# EndEffector.net
KiCad netlist of a schematic drawn in EAGLE
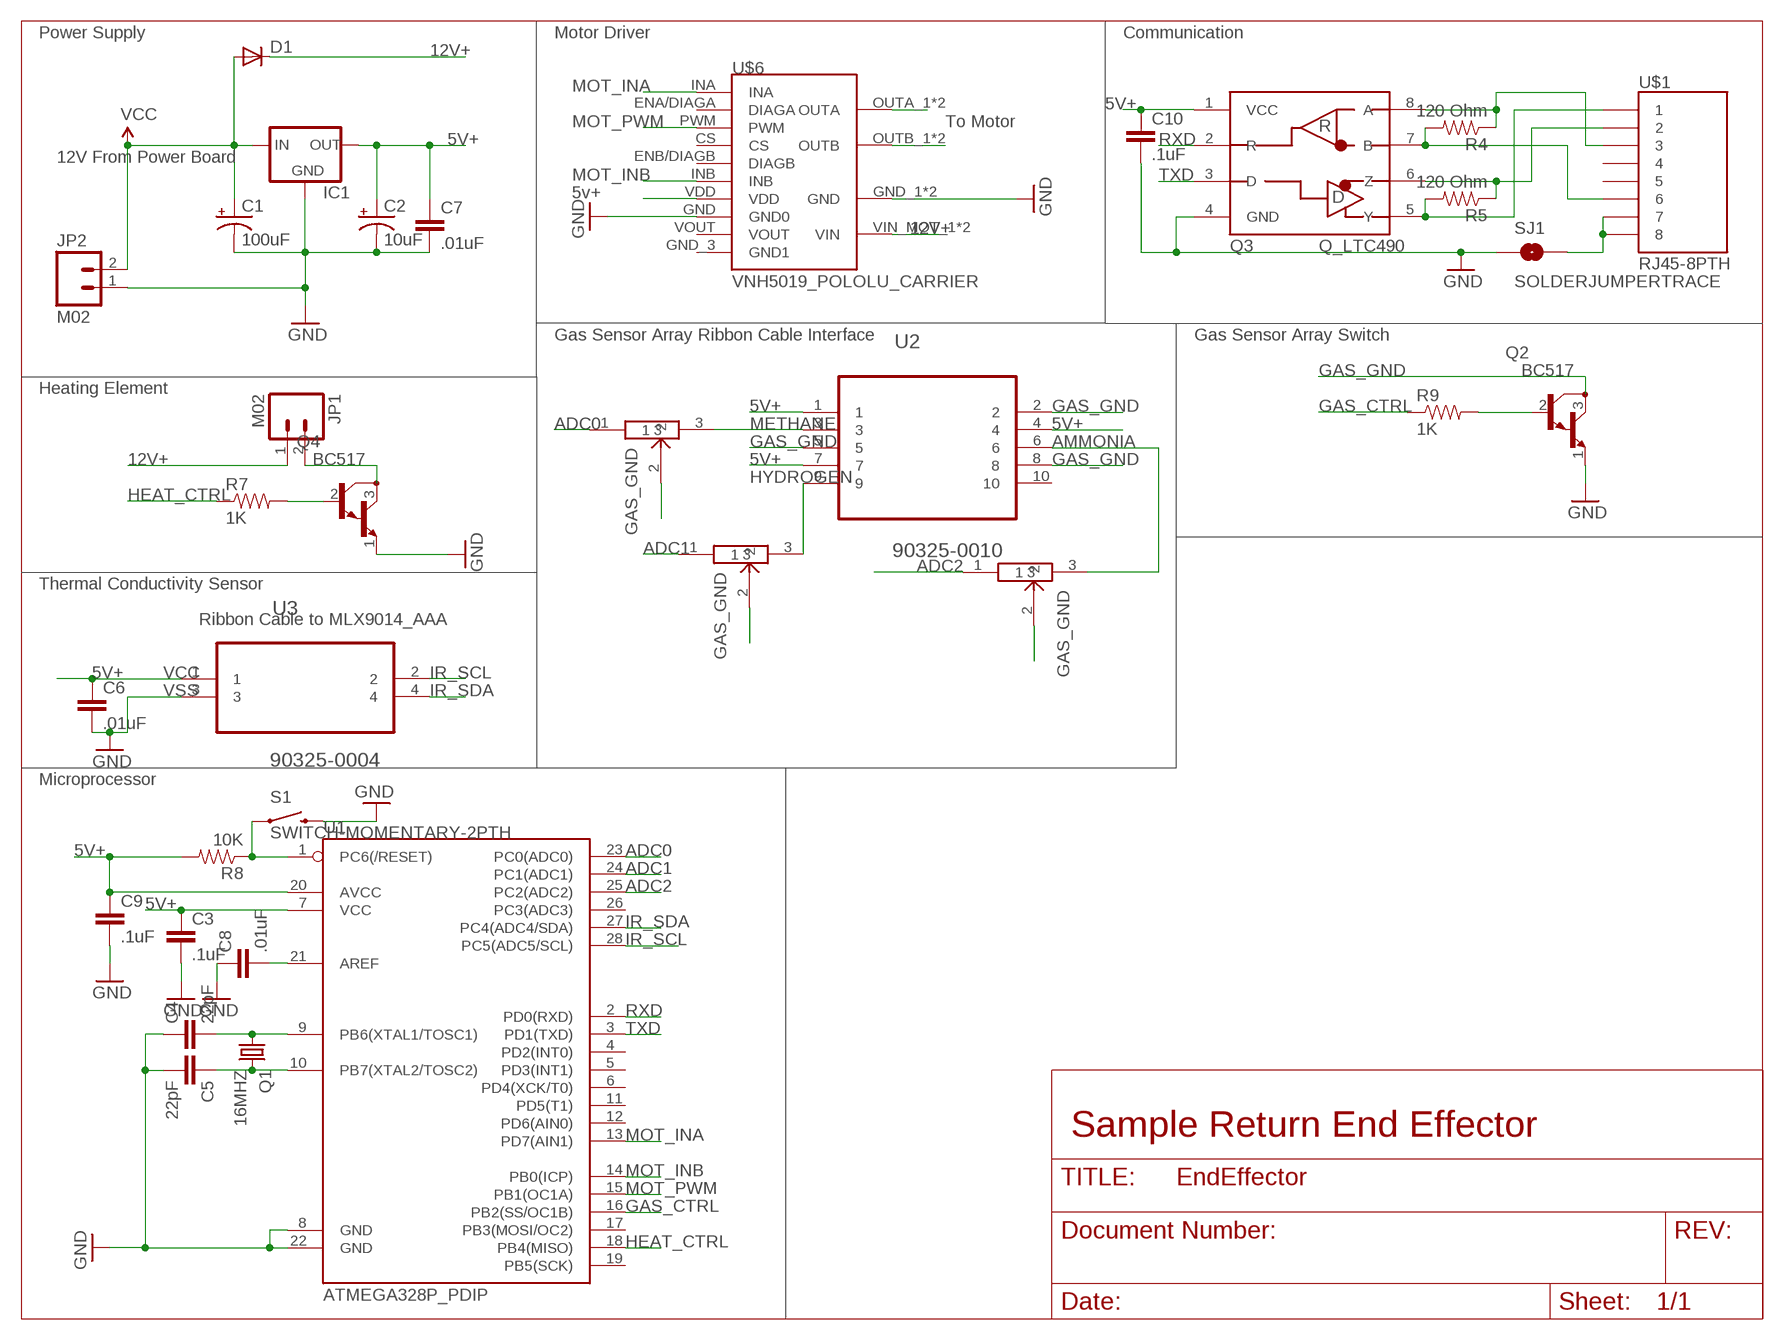
[diagram p0: schematic, sheet 1]

(export (version "E")
  (design (tool "Eeschema 10.0.6"))
  (components
    (comp (ref "C1")
      (value "100uF")
      (footprint "eagle-import:CPOL-RADIAL-100UF-25V")
      (libsource (lib "eagle-import") (part "CAP_POLPTH1"))
    )
    (comp (ref "C2")
      (value "10uF")
      (footprint "eagle-import:CPOL-RADIAL-10UF-25V")
      (libsource (lib "eagle-import") (part "CAP_POLPTH2"))
    )
    (comp (ref "C3")
      (value ".1uF")
      (footprint "eagle-import:CAP-PTH-SMALL-KIT")
      (libsource (lib "eagle-import") (part "CAPKIT"))
    )
    (comp (ref "C4")
      (value "22pF")
      (footprint "eagle-import:CAP-PTH-SMALL-KIT")
      (libsource (lib "eagle-import") (part "CAPKIT"))
    )
    (comp (ref "C5")
      (value "22pF")
      (footprint "eagle-import:CAP-PTH-SMALL-KIT")
      (libsource (lib "eagle-import") (part "CAPKIT"))
    )
    (comp (ref "C6")
      (value ".01uF")
      (footprint "eagle-import:CAP-PTH-SMALL-KIT")
      (libsource (lib "eagle-import") (part "CAPKIT"))
    )
    (comp (ref "C7")
      (value ".01uF")
      (footprint "eagle-import:CAP-PTH-SMALL-KIT")
      (libsource (lib "eagle-import") (part "CAPKIT"))
    )
    (comp (ref "C8")
      (value ".01uF")
      (footprint "eagle-import:CAP-PTH-SMALL-KIT")
      (libsource (lib "eagle-import") (part "CAPKIT"))
    )
    (comp (ref "C9")
      (value ".1uF")
      (footprint "eagle-import:CAP-PTH-SMALL-KIT")
      (libsource (lib "eagle-import") (part "CAPKIT"))
    )
    (comp (ref "C10")
      (value ".1uF")
      (footprint "eagle-import:CAP-PTH-SMALL-KIT")
      (libsource (lib "eagle-import") (part "CAPKIT"))
    )
    (comp (ref "D1")
      (value "DIODEPTH")
      (footprint "eagle-import:DIODE-1N4001")
      (libsource (lib "eagle-import") (part "DIODEPTH"))
    )
    (comp (ref "IC1")
      (value "V_REG_78XXSINK")
      (footprint "eagle-import:TO220-IGO")
      (libsource (lib "eagle-import") (part "V_REG_78XXSINK"))
    )
    (comp (ref "JP1")
      (value "M02")
      (footprint "eagle-import:1X02_PP_HOLES_ONLY")
      (libsource (lib "eagle-import") (part "M02POGO_PIN_HOLES_ONLY"))
    )
    (comp (ref "JP2")
      (value "M02")
      (footprint "eagle-import:1X02_PP_HOLES_ONLY")
      (libsource (lib "eagle-import") (part "M02POGO_PIN_HOLES_ONLY"))
    )
    (comp (ref "Q1")
      (value "16MHZ")
      (footprint "eagle-import:HC49_S")
      (libsource (lib "eagle-import") (part "CRYSTALHC49S"))
    )
    (comp (ref "Q2")
      (value "BC517")
      (footprint "eagle-import:TO92")
      (libsource (lib "eagle-import") (part "BC517"))
    )
    (comp (ref "Q3")
      (value "Q_LTC490")
      (footprint "eagle-import:DIP8")
      (libsource (lib "eagle-import") (part "Q_LTC490"))
    )
    (comp (ref "Q4")
      (value "BC517")
      (footprint "eagle-import:TO92")
      (libsource (lib "eagle-import") (part "BC517"))
    )
    (comp (ref "R4")
      (value "120 Ohm")
      (footprint "eagle-import:AXIAL-0.3")
      (libsource (lib "eagle-import") (part "RESISTORAXIAL-0.3"))
    )
    (comp (ref "R5")
      (value "120 Ohm")
      (footprint "eagle-import:AXIAL-0.3")
      (libsource (lib "eagle-import") (part "RESISTORAXIAL-0.3"))
    )
    (comp (ref "R7")
      (value "1K")
      (footprint "eagle-import:AXIAL-0.3")
      (libsource (lib "eagle-import") (part "RESISTORAXIAL-0.3"))
    )
    (comp (ref "R8")
      (value "10K")
      (footprint "eagle-import:AXIAL-0.3")
      (libsource (lib "eagle-import") (part "RESISTORAXIAL-0.3"))
    )
    (comp (ref "R9")
      (value "1K")
      (footprint "eagle-import:AXIAL-0.3")
      (libsource (lib "eagle-import") (part "RESISTORAXIAL-0.3"))
    )
    (comp (ref "S1")
      (value "SWITCH-MOMENTARY-2PTH")
      (footprint "eagle-import:TACTILE-PTH")
      (libsource (lib "eagle-import") (part "SWITCH-MOMENTARY-2PTH"))
    )
    (comp (ref "SJ1")
      (value "SOLDERJUMPERTRACE")
      (footprint "eagle-import:SJ_2S-TRACE")
      (libsource (lib "eagle-import") (part "SOLDERJUMPERTRACE"))
    )
    (comp (ref "U$1")
      (value "RJ45-8PTH")
      (footprint "eagle-import:RJ45-8")
      (libsource (lib "eagle-import") (part "RJ45-8PTH"))
    )
    (comp (ref "U$2")
      (value "POTENTIOMETER_BOURNS_3006P-1-104LF")
      (footprint "eagle-import:BOURNS30006_TRIMPOT")
      (libsource (lib "eagle-import") (part "POTENTIOMETER_BOURNS_3006P-1-104LF"))
    )
    (comp (ref "U$4")
      (value "POTENTIOMETER_BOURNS_3006P-1-104LF")
      (footprint "eagle-import:BOURNS30006_TRIMPOT")
      (libsource (lib "eagle-import") (part "POTENTIOMETER_BOURNS_3006P-1-104LF"))
    )
    (comp (ref "U$5")
      (value "POTENTIOMETER_BOURNS_3006P-1-104LF")
      (footprint "eagle-import:BOURNS30006_TRIMPOT")
      (libsource (lib "eagle-import") (part "POTENTIOMETER_BOURNS_3006P-1-104LF"))
    )
    (comp (ref "U$6")
      (value "VNH5019_POLOLU_CARRIER")
      (footprint "eagle-import:VNH5019_CARRIER")
      (libsource (lib "eagle-import") (part "VNH5019_POLOLU_CARRIER"))
    )
    (comp (ref "U1")
      (value "ATMEGA328P_PDIP")
      (footprint "eagle-import:DIL28-3")
      (libsource (lib "eagle-import") (part "ATMEGA328P_PDIP"))
    )
    (comp (ref "U2")
      (value "90325-0010")
      (footprint "eagle-import:MOLEX_90325-0010")
      (libsource (lib "eagle-import") (part "90325-0010"))
    )
    (comp (ref "U3")
      (value "90325-0004")
      (footprint "eagle-import:MOLEX_90325-0004")
      (libsource (lib "eagle-import") (part "90325-0004"))
    )
  )
  (nets
    (net (code "1") (name "/5V+") (class "Default")
      (node (ref "C10") (pin "1") (pinfunction "1_1") (pintype "passive"))
      (node (ref "C2") (pin "1") (pinfunction "+_1") (pintype "passive"))
      (node (ref "C3") (pin "1") (pinfunction "1_1") (pintype "passive"))
      (node (ref "C6") (pin "1") (pinfunction "1_1") (pintype "passive"))
      (node (ref "C7") (pin "1") (pinfunction "1_1") (pintype "passive"))
      (node (ref "C9") (pin "1") (pinfunction "1_1") (pintype "passive"))
      (node (ref "IC1") (pin "OUT") (pinfunction "OUT_OUT") (pintype "output"))
      (node (ref "Q3") (pin "1") (pinfunction "VCC_1") (pintype "bidirectional"))
      (node (ref "R8") (pin "P$2") (pinfunction "2_P$2") (pintype "passive"))
      (node (ref "U$6") (pin "VDD") (pinfunction "VDD_VDD") (pintype "bidirectional"))
      (node (ref "U1") (pin "20") (pinfunction "AVCC_20") (pintype "bidirectional"))
      (node (ref "U1") (pin "7") (pinfunction "VCC_7") (pintype "bidirectional"))
      (node (ref "U2") (pin "1") (pinfunction "1_1") (pintype "passive"))
      (node (ref "U2") (pin "4") (pinfunction "4_4") (pintype "passive"))
      (node (ref "U2") (pin "7") (pinfunction "7_7") (pintype "passive"))
      (node (ref "U3") (pin "1") (pinfunction "1_1") (pintype "passive"))
    )
    (net (code "2") (name "/12V+") (class "Default")
      (node (ref "D1") (pin "C") (pinfunction "C_C") (pintype "passive"))
      (node (ref "JP1") (pin "1") (pinfunction "1_1") (pintype "passive"))
      (node (ref "U$6") (pin "VIN_MOT_1") (pinfunction "VIN_VIN_MOT_1") (pintype "bidirectional"))
      (node (ref "U$6") (pin "VIN_MOT_2") (pinfunction "VIN_VIN_MOT_2") (pintype "bidirectional"))
    )
    (net (code "3") (name "/ADC0") (class "Default")
      (node (ref "U$4") (pin "1") (pinfunction "1_1") (pintype "bidirectional"))
      (node (ref "U1") (pin "23") (pinfunction "PC0(ADC0)_23") (pintype "bidirectional"))
    )
    (net (code "4") (name "/ADC1") (class "Default")
      (node (ref "U$5") (pin "1") (pinfunction "1_1") (pintype "bidirectional"))
      (node (ref "U1") (pin "24") (pinfunction "PC1(ADC1)_24") (pintype "bidirectional"))
    )
    (net (code "5") (name "/ADC2") (class "Default")
      (node (ref "U$2") (pin "1") (pinfunction "1_1") (pintype "bidirectional"))
      (node (ref "U1") (pin "25") (pinfunction "PC2(ADC2)_25") (pintype "bidirectional"))
    )
    (net (code "6") (name "/AMMONIA") (class "Default")
      (node (ref "U$2") (pin "3") (pinfunction "3_3") (pintype "bidirectional"))
      (node (ref "U2") (pin "6") (pinfunction "6_6") (pintype "passive"))
    )
    (net (code "7") (name "/GAS_CTRL") (class "Default")
      (node (ref "R9") (pin "P$1") (pinfunction "1_P$1") (pintype "passive"))
      (node (ref "U1") (pin "16") (pinfunction "PB2(SS/OC1B)_16") (pintype "bidirectional"))
    )
    (net (code "8") (name "/GAS_GND") (class "Default")
      (node (ref "Q2") (pin "3") (pinfunction "C_3") (pintype "passive"))
      (node (ref "U$2") (pin "2") (pinfunction "2_2") (pintype "bidirectional"))
      (node (ref "U$4") (pin "2") (pinfunction "2_2") (pintype "bidirectional"))
      (node (ref "U$5") (pin "2") (pinfunction "2_2") (pintype "bidirectional"))
      (node (ref "U2") (pin "2") (pinfunction "2_2") (pintype "passive"))
      (node (ref "U2") (pin "5") (pinfunction "5_5") (pintype "passive"))
      (node (ref "U2") (pin "8") (pinfunction "8_8") (pintype "passive"))
    )
    (net (code "9") (name "/HEAT_CTRL") (class "Default")
      (node (ref "R7") (pin "P$1") (pinfunction "1_P$1") (pintype "passive"))
      (node (ref "U1") (pin "18") (pinfunction "PB4(MISO)_18") (pintype "bidirectional"))
    )
    (net (code "10") (name "/HYDROGEN") (class "Default")
      (node (ref "U$5") (pin "3") (pinfunction "3_3") (pintype "bidirectional"))
      (node (ref "U2") (pin "9") (pinfunction "9_9") (pintype "passive"))
    )
    (net (code "11") (name "/IR_SCL") (class "Default")
      (node (ref "U1") (pin "28") (pinfunction "PC5(ADC5/SCL)_28") (pintype "bidirectional"))
      (node (ref "U3") (pin "2") (pinfunction "2_2") (pintype "passive"))
    )
    (net (code "12") (name "/IR_SDA") (class "Default")
      (node (ref "U1") (pin "27") (pinfunction "PC4(ADC4/SDA)_27") (pintype "bidirectional"))
      (node (ref "U3") (pin "4") (pinfunction "4_4") (pintype "passive"))
    )
    (net (code "13") (name "/METHANE") (class "Default")
      (node (ref "U$4") (pin "3") (pinfunction "3_3") (pintype "bidirectional"))
      (node (ref "U2") (pin "3") (pinfunction "3_3") (pintype "passive"))
    )
    (net (code "14") (name "/MOT_INA") (class "Default")
      (node (ref "U$6") (pin "INA") (pinfunction "INA_INA") (pintype "bidirectional"))
      (node (ref "U1") (pin "13") (pinfunction "PD7(AIN1)_13") (pintype "bidirectional"))
    )
    (net (code "15") (name "/MOT_INB") (class "Default")
      (node (ref "U$6") (pin "INB") (pinfunction "INB_INB") (pintype "bidirectional"))
      (node (ref "U1") (pin "14") (pinfunction "PB0(ICP)_14") (pintype "bidirectional"))
    )
    (net (code "16") (name "/MOT_PWM") (class "Default")
      (node (ref "U$6") (pin "PWM") (pinfunction "PWM_PWM") (pintype "bidirectional"))
      (node (ref "U1") (pin "15") (pinfunction "PB1(OC1A)_15") (pintype "bidirectional"))
    )
    (net (code "17") (name "/RXD") (class "Default")
      (node (ref "Q3") (pin "2") (pinfunction "R_2") (pintype "bidirectional"))
      (node (ref "U1") (pin "2") (pinfunction "PD0(RXD)_2") (pintype "bidirectional"))
    )
    (net (code "18") (name "/TXD") (class "Default")
      (node (ref "Q3") (pin "3") (pinfunction "D_3") (pintype "bidirectional"))
      (node (ref "U1") (pin "3") (pinfunction "PD1(TXD)_3") (pintype "bidirectional"))
    )
    (net (code "19") (name "GND") (class "Default")
      (node (ref "C1") (pin "2") (pinfunction "-_2") (pintype "passive"))
      (node (ref "C10") (pin "2") (pinfunction "2_2") (pintype "passive"))
      (node (ref "C2") (pin "2") (pinfunction "-_2") (pintype "passive"))
      (node (ref "C3") (pin "2") (pinfunction "2_2") (pintype "passive"))
      (node (ref "C4") (pin "1") (pinfunction "1_1") (pintype "passive"))
      (node (ref "C5") (pin "2") (pinfunction "2_2") (pintype "passive"))
      (node (ref "C6") (pin "2") (pinfunction "2_2") (pintype "passive"))
      (node (ref "C7") (pin "2") (pinfunction "2_2") (pintype "passive"))
      (node (ref "C8") (pin "1") (pinfunction "1_1") (pintype "passive"))
      (node (ref "C9") (pin "2") (pinfunction "2_2") (pintype "passive"))
      (node (ref "IC1") (pin "GND") (pinfunction "GND_GND") (pintype "input"))
      (node (ref "JP2") (pin "1") (pinfunction "1_1") (pintype "passive"))
      (node (ref "Q2") (pin "1") (pinfunction "E_1") (pintype "passive"))
      (node (ref "Q3") (pin "4") (pinfunction "GND_4") (pintype "bidirectional"))
      (node (ref "Q4") (pin "1") (pinfunction "E_1") (pintype "passive"))
      (node (ref "S1") (pin "3") (pinfunction "2_3") (pintype "passive"))
      (node (ref "SJ1") (pin "1") (pinfunction "1_1") (pintype "passive"))
      (node (ref "U$6") (pin "GND") (pinfunction "GND0_GND") (pintype "bidirectional"))
      (node (ref "U$6") (pin "GND_1") (pinfunction "GND_GND_1") (pintype "bidirectional"))
      (node (ref "U$6") (pin "GND_2") (pinfunction "GND_GND_2") (pintype "bidirectional"))
      (node (ref "U1") (pin "22") (pinfunction "GND_22") (pintype "bidirectional"))
      (node (ref "U1") (pin "8") (pinfunction "GND_8") (pintype "bidirectional"))
      (node (ref "U3") (pin "3") (pinfunction "3_3") (pintype "passive"))
    )
    (net (code "20") (name "Net-(Q2-B)") (class "Default")
      (node (ref "Q2") (pin "2") (pinfunction "B_2") (pintype "passive"))
      (node (ref "R9") (pin "P$2") (pinfunction "2_P$2") (pintype "passive"))
    )
    (net (code "21") (name "Net-(Q3-A)") (class "Default")
      (node (ref "Q3") (pin "8") (pinfunction "A_8") (pintype "bidirectional"))
      (node (ref "R4") (pin "P$1") (pinfunction "1_P$1") (pintype "passive"))
      (node (ref "U$1") (pin "3") (pinfunction "3_3") (pintype "bidirectional"))
    )
    (net (code "22") (name "Net-(Q3-B)") (class "Default")
      (node (ref "Q3") (pin "7") (pinfunction "B_7") (pintype "bidirectional"))
      (node (ref "R4") (pin "P$2") (pinfunction "2_P$2") (pintype "passive"))
      (node (ref "U$1") (pin "6") (pinfunction "6_6") (pintype "bidirectional"))
    )
    (net (code "23") (name "Net-(Q3-Y)") (class "Default")
      (node (ref "Q3") (pin "5") (pinfunction "Y_5") (pintype "bidirectional"))
      (node (ref "R5") (pin "P$2") (pinfunction "2_P$2") (pintype "passive"))
      (node (ref "U$1") (pin "1") (pinfunction "1_1") (pintype "bidirectional"))
    )
    (net (code "24") (name "Net-(Q3-Z)") (class "Default")
      (node (ref "Q3") (pin "6") (pinfunction "Z_6") (pintype "bidirectional"))
      (node (ref "R5") (pin "P$1") (pinfunction "1_P$1") (pintype "passive"))
      (node (ref "U$1") (pin "2") (pinfunction "2_2") (pintype "bidirectional"))
    )
    (net (code "25") (name "Net-(Q4-B)") (class "Default")
      (node (ref "Q4") (pin "2") (pinfunction "B_2") (pintype "passive"))
      (node (ref "R7") (pin "P$2") (pinfunction "2_P$2") (pintype "passive"))
    )
    (net (code "26") (name "Net-(Q4-C)") (class "Default")
      (node (ref "JP1") (pin "2") (pinfunction "2_2") (pintype "passive"))
      (node (ref "Q4") (pin "3") (pinfunction "C_3") (pintype "passive"))
    )
    (net (code "27") (name "Net-(R8-1)") (class "Default")
      (node (ref "R8") (pin "P$1") (pinfunction "1_P$1") (pintype "passive"))
      (node (ref "S1") (pin "1") (pinfunction "1_1") (pintype "passive"))
      (node (ref "U1") (pin "1") (pinfunction "PC6(/RESET)_1") (pintype "bidirectional"))
    )
    (net (code "28") (name "Net-(SJ1-Pad2)") (class "Default")
      (node (ref "SJ1") (pin "2") (pinfunction "2_2") (pintype "passive"))
      (node (ref "U$1") (pin "7") (pinfunction "7_7") (pintype "bidirectional"))
      (node (ref "U$1") (pin "8") (pinfunction "8_8") (pintype "bidirectional"))
    )
    (net (code "29") (name "Net-(U$6-OUTA-PadOUTA_1)") (class "Default")
      (node (ref "U$6") (pin "OUTA_1") (pinfunction "OUTA_OUTA_1") (pintype "bidirectional"))
      (node (ref "U$6") (pin "OUTA_2") (pinfunction "OUTA_OUTA_2") (pintype "bidirectional"))
    )
    (net (code "30") (name "Net-(U$6-OUTB-PadOUTB_1)") (class "Default")
      (node (ref "U$6") (pin "OUTB_1") (pinfunction "OUTB_OUTB_1") (pintype "bidirectional"))
      (node (ref "U$6") (pin "OUTB_2") (pinfunction "OUTB_OUTB_2") (pintype "bidirectional"))
    )
    (net (code "31") (name "Net-(U1-AREF)") (class "Default")
      (node (ref "C8") (pin "2") (pinfunction "2_2") (pintype "passive"))
      (node (ref "U1") (pin "21") (pinfunction "AREF_21") (pintype "bidirectional"))
    )
    (net (code "32") (name "Net-(U1-PB6(XTAL1{slash}TOSC1))") (class "Default")
      (node (ref "C4") (pin "2") (pinfunction "2_2") (pintype "passive"))
      (node (ref "Q1") (pin "1") (pinfunction "1_1") (pintype "passive"))
      (node (ref "U1") (pin "9") (pinfunction "PB6(XTAL1/TOSC1)_9") (pintype "bidirectional"))
    )
    (net (code "33") (name "Net-(U1-PB7(XTAL2{slash}TOSC2))") (class "Default")
      (node (ref "C5") (pin "1") (pinfunction "1_1") (pintype "passive"))
      (node (ref "Q1") (pin "2") (pinfunction "2_2") (pintype "passive"))
      (node (ref "U1") (pin "10") (pinfunction "PB7(XTAL2/TOSC2)_10") (pintype "bidirectional"))
    )
    (net (code "34") (name "VCC") (class "Default")
      (node (ref "C1") (pin "1") (pinfunction "+_1") (pintype "passive"))
      (node (ref "D1") (pin "A") (pinfunction "A_A") (pintype "passive"))
      (node (ref "IC1") (pin "IN") (pinfunction "IN_IN") (pintype "input"))
      (node (ref "JP2") (pin "2") (pinfunction "2_2") (pintype "passive"))
    )
    (net (code "35") (name "unconnected-(U$1-Pad4)") (class "Default")
      (node (ref "U$1") (pin "4") (pinfunction "4_4") (pintype "bidirectional"))
    )
    (net (code "36") (name "unconnected-(U$1-Pad5)") (class "Default")
      (node (ref "U$1") (pin "5") (pinfunction "5_5") (pintype "bidirectional"))
    )
    (net (code "37") (name "unconnected-(U$6-DIAGA-PadENA{slash}DIAGA)") (class "Default")
      (node (ref "U$6") (pin "ENA/DIAGA") (pinfunction "DIAGA_ENA/DIAGA") (pintype "bidirectional"))
    )
    (net (code "38") (name "unconnected-(U$6-DIAGB-PadENB{slash}DIAGB)") (class "Default")
      (node (ref "U$6") (pin "ENB/DIAGB") (pinfunction "DIAGB_ENB/DIAGB") (pintype "bidirectional"))
    )
    (net (code "39") (name "unconnected-(U$6-GND1-PadGND_3)") (class "Default")
      (node (ref "U$6") (pin "GND_3") (pinfunction "GND1_GND_3") (pintype "bidirectional"))
    )
    (net (code "40") (name "unconnected-(U$6-PadCS)") (class "Default")
      (node (ref "U$6") (pin "CS") (pinfunction "CS_CS") (pintype "bidirectional"))
    )
    (net (code "41") (name "unconnected-(U$6-PadVOUT)") (class "Default")
      (node (ref "U$6") (pin "VOUT") (pinfunction "VOUT_VOUT") (pintype "bidirectional"))
    )
    (net (code "42") (name "unconnected-(U1-PB3(MOSI{slash}OC2)-Pad17)") (class "Default")
      (node (ref "U1") (pin "17") (pinfunction "PB3(MOSI/OC2)_17") (pintype "bidirectional"))
    )
    (net (code "43") (name "unconnected-(U1-PB5(SCK)-Pad19)") (class "Default")
      (node (ref "U1") (pin "19") (pinfunction "PB5(SCK)_19") (pintype "bidirectional"))
    )
    (net (code "44") (name "unconnected-(U1-PC3(ADC3)-Pad26)") (class "Default")
      (node (ref "U1") (pin "26") (pinfunction "PC3(ADC3)_26") (pintype "bidirectional"))
    )
    (net (code "45") (name "unconnected-(U1-PD2(INT0)-Pad4)") (class "Default")
      (node (ref "U1") (pin "4") (pinfunction "PD2(INT0)_4") (pintype "bidirectional"))
    )
    (net (code "46") (name "unconnected-(U1-PD3(INT1)-Pad5)") (class "Default")
      (node (ref "U1") (pin "5") (pinfunction "PD3(INT1)_5") (pintype "bidirectional"))
    )
    (net (code "47") (name "unconnected-(U1-PD4(XCK{slash}T0)-Pad6)") (class "Default")
      (node (ref "U1") (pin "6") (pinfunction "PD4(XCK/T0)_6") (pintype "bidirectional"))
    )
    (net (code "48") (name "unconnected-(U1-PD5(T1)-Pad11)") (class "Default")
      (node (ref "U1") (pin "11") (pinfunction "PD5(T1)_11") (pintype "bidirectional"))
    )
    (net (code "49") (name "unconnected-(U1-PD6(AIN0)-Pad12)") (class "Default")
      (node (ref "U1") (pin "12") (pinfunction "PD6(AIN0)_12") (pintype "bidirectional"))
    )
    (net (code "50") (name "unconnected-(U2-Pad10)") (class "Default")
      (node (ref "U2") (pin "10") (pinfunction "10_10") (pintype "passive"))
    )
  )
)
